# PowerRouting.net
KiCad netlist of a schematic drawn in Altium Designer
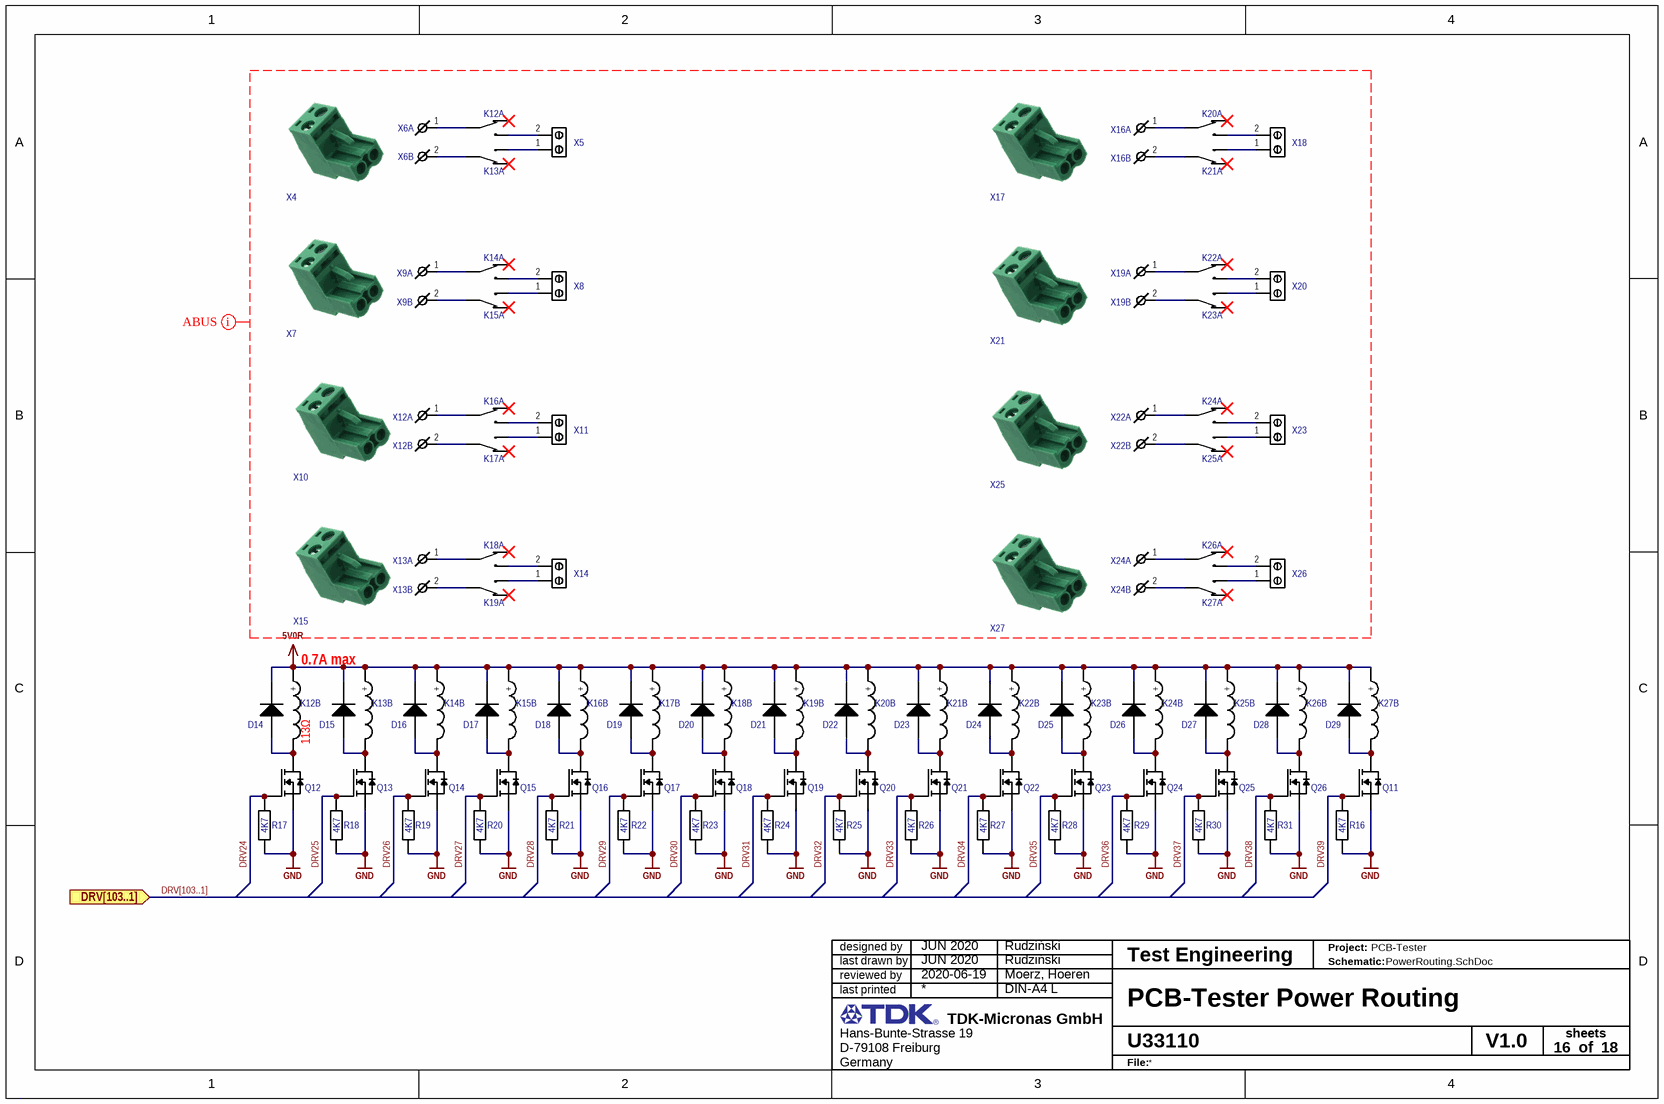
[diagram p0: PowerRouting.SchDoc]

(export (version "E")
  (design (tool "Eeschema 10.0.6"))
  (components
    (comp (ref "D14")
      (value "D")
      (footprint "SOD123")
      (description "DIODE GEN PURP 100V 300MA SOD123")
      (fields
        (field (name "02. DISTRIBUTOR PART NUMBER") "1N4148W-FDICT-ND")
        (field (name "07. MANUFACTURER  PART NUMBER") "1N4148W-7-F")
      )
      (libsource (lib "PCB-Tester-Board-V1") (part "1N4148W"))
    )
    (comp (ref "D15")
      (value "D")
      (footprint "SOD123")
      (description "DIODE GEN PURP 100V 300MA SOD123")
      (fields
        (field (name "02. DISTRIBUTOR PART NUMBER") "1N4148W-FDICT-ND")
        (field (name "07. MANUFACTURER  PART NUMBER") "1N4148W-7-F")
      )
      (libsource (lib "PCB-Tester-Board-V1") (part "1N4148W"))
    )
    (comp (ref "D16")
      (value "D")
      (footprint "SOD123")
      (description "DIODE GEN PURP 100V 300MA SOD123")
      (fields
        (field (name "02. DISTRIBUTOR PART NUMBER") "1N4148W-FDICT-ND")
        (field (name "07. MANUFACTURER  PART NUMBER") "1N4148W-7-F")
      )
      (libsource (lib "PCB-Tester-Board-V1") (part "1N4148W"))
    )
    (comp (ref "D17")
      (value "D")
      (footprint "SOD123")
      (description "DIODE GEN PURP 100V 300MA SOD123")
      (fields
        (field (name "02. DISTRIBUTOR PART NUMBER") "1N4148W-FDICT-ND")
        (field (name "07. MANUFACTURER  PART NUMBER") "1N4148W-7-F")
      )
      (libsource (lib "PCB-Tester-Board-V1") (part "1N4148W"))
    )
    (comp (ref "D18")
      (value "D")
      (footprint "SOD123")
      (description "DIODE GEN PURP 100V 300MA SOD123")
      (fields
        (field (name "02. DISTRIBUTOR PART NUMBER") "1N4148W-FDICT-ND")
        (field (name "07. MANUFACTURER  PART NUMBER") "1N4148W-7-F")
      )
      (libsource (lib "PCB-Tester-Board-V1") (part "1N4148W"))
    )
    (comp (ref "D19")
      (value "D")
      (footprint "SOD123")
      (description "DIODE GEN PURP 100V 300MA SOD123")
      (fields
        (field (name "02. DISTRIBUTOR PART NUMBER") "1N4148W-FDICT-ND")
        (field (name "07. MANUFACTURER  PART NUMBER") "1N4148W-7-F")
      )
      (libsource (lib "PCB-Tester-Board-V1") (part "1N4148W"))
    )
    (comp (ref "D20")
      (value "D")
      (footprint "SOD123")
      (description "DIODE GEN PURP 100V 300MA SOD123")
      (fields
        (field (name "02. DISTRIBUTOR PART NUMBER") "1N4148W-FDICT-ND")
        (field (name "07. MANUFACTURER  PART NUMBER") "1N4148W-7-F")
      )
      (libsource (lib "PCB-Tester-Board-V1") (part "1N4148W"))
    )
    (comp (ref "D21")
      (value "D")
      (footprint "SOD123")
      (description "DIODE GEN PURP 100V 300MA SOD123")
      (fields
        (field (name "02. DISTRIBUTOR PART NUMBER") "1N4148W-FDICT-ND")
        (field (name "07. MANUFACTURER  PART NUMBER") "1N4148W-7-F")
      )
      (libsource (lib "PCB-Tester-Board-V1") (part "1N4148W"))
    )
    (comp (ref "D22")
      (value "D")
      (footprint "SOD123")
      (description "DIODE GEN PURP 100V 300MA SOD123")
      (fields
        (field (name "02. DISTRIBUTOR PART NUMBER") "1N4148W-FDICT-ND")
        (field (name "07. MANUFACTURER  PART NUMBER") "1N4148W-7-F")
      )
      (libsource (lib "PCB-Tester-Board-V1") (part "1N4148W"))
    )
    (comp (ref "D23")
      (value "D")
      (footprint "SOD123")
      (description "DIODE GEN PURP 100V 300MA SOD123")
      (fields
        (field (name "02. DISTRIBUTOR PART NUMBER") "1N4148W-FDICT-ND")
        (field (name "07. MANUFACTURER  PART NUMBER") "1N4148W-7-F")
      )
      (libsource (lib "PCB-Tester-Board-V1") (part "1N4148W"))
    )
    (comp (ref "D24")
      (value "D")
      (footprint "SOD123")
      (description "DIODE GEN PURP 100V 300MA SOD123")
      (fields
        (field (name "02. DISTRIBUTOR PART NUMBER") "1N4148W-FDICT-ND")
        (field (name "07. MANUFACTURER  PART NUMBER") "1N4148W-7-F")
      )
      (libsource (lib "PCB-Tester-Board-V1") (part "1N4148W"))
    )
    (comp (ref "D25")
      (value "D")
      (footprint "SOD123")
      (description "DIODE GEN PURP 100V 300MA SOD123")
      (fields
        (field (name "02. DISTRIBUTOR PART NUMBER") "1N4148W-FDICT-ND")
        (field (name "07. MANUFACTURER  PART NUMBER") "1N4148W-7-F")
      )
      (libsource (lib "PCB-Tester-Board-V1") (part "1N4148W"))
    )
    (comp (ref "D26")
      (value "D")
      (footprint "SOD123")
      (description "DIODE GEN PURP 100V 300MA SOD123")
      (fields
        (field (name "02. DISTRIBUTOR PART NUMBER") "1N4148W-FDICT-ND")
        (field (name "07. MANUFACTURER  PART NUMBER") "1N4148W-7-F")
      )
      (libsource (lib "PCB-Tester-Board-V1") (part "1N4148W"))
    )
    (comp (ref "D27")
      (value "D")
      (footprint "SOD123")
      (description "DIODE GEN PURP 100V 300MA SOD123")
      (fields
        (field (name "02. DISTRIBUTOR PART NUMBER") "1N4148W-FDICT-ND")
        (field (name "07. MANUFACTURER  PART NUMBER") "1N4148W-7-F")
      )
      (libsource (lib "PCB-Tester-Board-V1") (part "1N4148W"))
    )
    (comp (ref "D28")
      (value "D")
      (footprint "SOD123")
      (description "DIODE GEN PURP 100V 300MA SOD123")
      (fields
        (field (name "02. DISTRIBUTOR PART NUMBER") "1N4148W-FDICT-ND")
        (field (name "07. MANUFACTURER  PART NUMBER") "1N4148W-7-F")
      )
      (libsource (lib "PCB-Tester-Board-V1") (part "1N4148W"))
    )
    (comp (ref "D29")
      (value "D")
      (footprint "SOD123")
      (description "DIODE GEN PURP 100V 300MA SOD123")
      (fields
        (field (name "02. DISTRIBUTOR PART NUMBER") "1N4148W-FDICT-ND")
        (field (name "07. MANUFACTURER  PART NUMBER") "1N4148W-7-F")
      )
      (libsource (lib "PCB-Tester-Board-V1") (part "1N4148W"))
    )
    (comp (ref "K12")
      (value "K")
      (footprint "HF118F005-1ZS1")
      (description "5V Power Relay, switch over")
      (fields
        (field (name "02. DISTRIBUTOR PART NUMBER") "176-2821")
        (field (name "07. MANUFACTURER  PART NUMBER") "HF118F/005-1ZS1T(136)")
        (field (name "COIL RESISTANCE") "113Ω")
        (field (name "13. CREATED DATE/NAME") "AUG2018/Hören")
      )
      (libsource (lib "chickenfood") (part "HF118F005-1ZS1"))
    )
    (comp (ref "K13")
      (value "K")
      (footprint "HF118F005-1ZS1")
      (description "5V Power Relay, switch over")
      (fields
        (field (name "02. DISTRIBUTOR PART NUMBER") "176-2821")
        (field (name "07. MANUFACTURER  PART NUMBER") "HF118F/005-1ZS1T(136)")
        (field (name "13. CREATED DATE/NAME") "AUG2018/Hören")
      )
      (libsource (lib "") (part "HF118F005-1ZS1_1"))
    )
    (comp (ref "K14")
      (value "K")
      (footprint "HF118F005-1ZS1")
      (description "5V Power Relay, switch over")
      (fields
        (field (name "02. DISTRIBUTOR PART NUMBER") "176-2821")
        (field (name "07. MANUFACTURER  PART NUMBER") "HF118F/005-1ZS1T(136)")
        (field (name "13. CREATED DATE/NAME") "AUG2018/Hören")
      )
      (libsource (lib "chickenfood") (part "HF118F005-1ZS1"))
    )
    (comp (ref "K15")
      (value "K")
      (footprint "HF118F005-1ZS1")
      (description "5V Power Relay, switch over")
      (fields
        (field (name "02. DISTRIBUTOR PART NUMBER") "176-2821")
        (field (name "07. MANUFACTURER  PART NUMBER") "HF118F/005-1ZS1T(136)")
        (field (name "13. CREATED DATE/NAME") "AUG2018/Hören")
      )
      (libsource (lib "chickenfood") (part "HF118F005-1ZS1"))
    )
    (comp (ref "K16")
      (value "K")
      (footprint "HF118F005-1ZS1")
      (description "5V Power Relay, switch over")
      (fields
        (field (name "02. DISTRIBUTOR PART NUMBER") "176-2821")
        (field (name "07. MANUFACTURER  PART NUMBER") "HF118F/005-1ZS1T(136)")
        (field (name "13. CREATED DATE/NAME") "AUG2018/Hören")
      )
      (libsource (lib "chickenfood") (part "HF118F005-1ZS1"))
    )
    (comp (ref "K17")
      (value "K")
      (footprint "HF118F005-1ZS1")
      (description "5V Power Relay, switch over")
      (fields
        (field (name "02. DISTRIBUTOR PART NUMBER") "176-2821")
        (field (name "07. MANUFACTURER  PART NUMBER") "HF118F/005-1ZS1T(136)")
        (field (name "13. CREATED DATE/NAME") "AUG2018/Hören")
      )
      (libsource (lib "") (part "HF118F005-1ZS1_1"))
    )
    (comp (ref "K18")
      (value "K")
      (footprint "HF118F005-1ZS1")
      (description "5V Power Relay, switch over")
      (fields
        (field (name "02. DISTRIBUTOR PART NUMBER") "176-2821")
        (field (name "07. MANUFACTURER  PART NUMBER") "HF118F/005-1ZS1T(136)")
        (field (name "13. CREATED DATE/NAME") "AUG2018/Hören")
      )
      (libsource (lib "chickenfood") (part "HF118F005-1ZS1"))
    )
    (comp (ref "K19")
      (value "K")
      (footprint "HF118F005-1ZS1")
      (description "5V Power Relay, switch over")
      (fields
        (field (name "02. DISTRIBUTOR PART NUMBER") "176-2821")
        (field (name "07. MANUFACTURER  PART NUMBER") "HF118F/005-1ZS1T(136)")
        (field (name "13. CREATED DATE/NAME") "AUG2018/Hören")
      )
      (libsource (lib "chickenfood") (part "HF118F005-1ZS1"))
    )
    (comp (ref "K20")
      (value "K")
      (footprint "HF118F005-1ZS1")
      (description "5V Power Relay, switch over")
      (fields
        (field (name "02. DISTRIBUTOR PART NUMBER") "176-2821")
        (field (name "07. MANUFACTURER  PART NUMBER") "HF118F/005-1ZS1T(136)")
        (field (name "13. CREATED DATE/NAME") "AUG2018/Hören")
      )
      (libsource (lib "chickenfood") (part "HF118F005-1ZS1"))
    )
    (comp (ref "K21")
      (value "K")
      (footprint "HF118F005-1ZS1")
      (description "5V Power Relay, switch over")
      (fields
        (field (name "02. DISTRIBUTOR PART NUMBER") "176-2821")
        (field (name "07. MANUFACTURER  PART NUMBER") "HF118F/005-1ZS1T(136)")
        (field (name "13. CREATED DATE/NAME") "AUG2018/Hören")
      )
      (libsource (lib "chickenfood") (part "HF118F005-1ZS1"))
    )
    (comp (ref "K22")
      (value "K")
      (footprint "HF118F005-1ZS1")
      (description "5V Power Relay, switch over")
      (fields
        (field (name "02. DISTRIBUTOR PART NUMBER") "176-2821")
        (field (name "07. MANUFACTURER  PART NUMBER") "HF118F/005-1ZS1T(136)")
        (field (name "13. CREATED DATE/NAME") "AUG2018/Hören")
      )
      (libsource (lib "chickenfood") (part "HF118F005-1ZS1"))
    )
    (comp (ref "K23")
      (value "K")
      (footprint "HF118F005-1ZS1")
      (description "5V Power Relay, switch over")
      (fields
        (field (name "02. DISTRIBUTOR PART NUMBER") "176-2821")
        (field (name "07. MANUFACTURER  PART NUMBER") "HF118F/005-1ZS1T(136)")
        (field (name "13. CREATED DATE/NAME") "AUG2018/Hören")
      )
      (libsource (lib "chickenfood") (part "HF118F005-1ZS1"))
    )
    (comp (ref "K24")
      (value "K")
      (footprint "HF118F005-1ZS1")
      (description "5V Power Relay, switch over")
      (fields
        (field (name "02. DISTRIBUTOR PART NUMBER") "176-2821")
        (field (name "07. MANUFACTURER  PART NUMBER") "HF118F/005-1ZS1T(136)")
        (field (name "13. CREATED DATE/NAME") "AUG2018/Hören")
      )
      (libsource (lib "chickenfood") (part "HF118F005-1ZS1"))
    )
    (comp (ref "K25")
      (value "K")
      (footprint "HF118F005-1ZS1")
      (description "5V Power Relay, switch over")
      (fields
        (field (name "02. DISTRIBUTOR PART NUMBER") "176-2821")
        (field (name "07. MANUFACTURER  PART NUMBER") "HF118F/005-1ZS1T(136)")
        (field (name "13. CREATED DATE/NAME") "AUG2018/Hören")
      )
      (libsource (lib "") (part "HF118F005-1ZS1_1"))
    )
    (comp (ref "K26")
      (value "K")
      (footprint "HF118F005-1ZS1")
      (description "5V Power Relay, switch over")
      (fields
        (field (name "02. DISTRIBUTOR PART NUMBER") "176-2821")
        (field (name "07. MANUFACTURER  PART NUMBER") "HF118F/005-1ZS1T(136)")
        (field (name "13. CREATED DATE/NAME") "AUG2018/Hören")
      )
      (libsource (lib "chickenfood") (part "HF118F005-1ZS1"))
    )
    (comp (ref "K27")
      (value "K")
      (footprint "HF118F005-1ZS1")
      (description "5V Power Relay, switch over")
      (fields
        (field (name "02. DISTRIBUTOR PART NUMBER") "176-2821")
        (field (name "07. MANUFACTURER  PART NUMBER") "HF118F/005-1ZS1T(136)")
        (field (name "13. CREATED DATE/NAME") "AUG2018/Hören")
      )
      (libsource (lib "") (part "HF118F005-1ZS1_1"))
    )
    (comp (ref "Q11")
      (value "Q")
      (footprint "SOT23-3")
      (description "MOSFET N-CH 25V 680MA SOT-23")
      (fields
        (field (name "02. DISTRIBUTOR PART NUMBER") "FDV303NDKR-ND")
        (field (name "07. MANUFACTURER  PART NUMBER") "FDV303N")
        (field (name "13. CREATED DATE/NAME") "AUG 2018 / Hören")
      )
      (libsource (lib "SCT8-Board1") (part "FDV303N"))
    )
    (comp (ref "Q12")
      (value "Q")
      (footprint "SOT23-3")
      (description "MOSFET N-CH 25V 680MA SOT-23")
      (fields
        (field (name "02. DISTRIBUTOR PART NUMBER") "FDV303NDKR-ND")
        (field (name "07. MANUFACTURER  PART NUMBER") "FDV303N")
        (field (name "13. CREATED DATE/NAME") "AUG 2018 / Hören")
      )
      (libsource (lib "SCT8-Board1") (part "FDV303N"))
    )
    (comp (ref "Q13")
      (value "Q")
      (footprint "SOT23-3")
      (description "MOSFET N-CH 25V 680MA SOT-23")
      (fields
        (field (name "02. DISTRIBUTOR PART NUMBER") "FDV303NDKR-ND")
        (field (name "07. MANUFACTURER  PART NUMBER") "FDV303N")
        (field (name "13. CREATED DATE/NAME") "AUG 2018 / Hören")
      )
      (libsource (lib "SCT8-Board1") (part "FDV303N"))
    )
    (comp (ref "Q14")
      (value "Q")
      (footprint "SOT23-3")
      (description "MOSFET N-CH 25V 680MA SOT-23")
      (fields
        (field (name "02. DISTRIBUTOR PART NUMBER") "FDV303NDKR-ND")
        (field (name "07. MANUFACTURER  PART NUMBER") "FDV303N")
        (field (name "13. CREATED DATE/NAME") "AUG 2018 / Hören")
      )
      (libsource (lib "SCT8-Board1") (part "FDV303N"))
    )
    (comp (ref "Q15")
      (value "Q")
      (footprint "SOT23-3")
      (description "MOSFET N-CH 25V 680MA SOT-23")
      (fields
        (field (name "02. DISTRIBUTOR PART NUMBER") "FDV303NDKR-ND")
        (field (name "07. MANUFACTURER  PART NUMBER") "FDV303N")
        (field (name "13. CREATED DATE/NAME") "AUG 2018 / Hören")
      )
      (libsource (lib "SCT8-Board1") (part "FDV303N"))
    )
    (comp (ref "Q16")
      (value "Q")
      (footprint "SOT23-3")
      (description "MOSFET N-CH 25V 680MA SOT-23")
      (fields
        (field (name "02. DISTRIBUTOR PART NUMBER") "FDV303NDKR-ND")
        (field (name "07. MANUFACTURER  PART NUMBER") "FDV303N")
        (field (name "13. CREATED DATE/NAME") "AUG 2018 / Hören")
      )
      (libsource (lib "SCT8-Board1") (part "FDV303N"))
    )
    (comp (ref "Q17")
      (value "Q")
      (footprint "SOT23-3")
      (description "MOSFET N-CH 25V 680MA SOT-23")
      (fields
        (field (name "02. DISTRIBUTOR PART NUMBER") "FDV303NDKR-ND")
        (field (name "07. MANUFACTURER  PART NUMBER") "FDV303N")
        (field (name "13. CREATED DATE/NAME") "AUG 2018 / Hören")
      )
      (libsource (lib "SCT8-Board1") (part "FDV303N"))
    )
    (comp (ref "Q18")
      (value "Q")
      (footprint "SOT23-3")
      (description "MOSFET N-CH 25V 680MA SOT-23")
      (fields
        (field (name "02. DISTRIBUTOR PART NUMBER") "FDV303NDKR-ND")
        (field (name "07. MANUFACTURER  PART NUMBER") "FDV303N")
        (field (name "13. CREATED DATE/NAME") "AUG 2018 / Hören")
      )
      (libsource (lib "SCT8-Board1") (part "FDV303N"))
    )
    (comp (ref "Q19")
      (value "Q")
      (footprint "SOT23-3")
      (description "MOSFET N-CH 25V 680MA SOT-23")
      (fields
        (field (name "02. DISTRIBUTOR PART NUMBER") "FDV303NDKR-ND")
        (field (name "07. MANUFACTURER  PART NUMBER") "FDV303N")
        (field (name "13. CREATED DATE/NAME") "AUG 2018 / Hören")
      )
      (libsource (lib "SCT8-Board1") (part "FDV303N"))
    )
    (comp (ref "Q20")
      (value "Q")
      (footprint "SOT23-3")
      (description "MOSFET N-CH 25V 680MA SOT-23")
      (fields
        (field (name "02. DISTRIBUTOR PART NUMBER") "FDV303NDKR-ND")
        (field (name "07. MANUFACTURER  PART NUMBER") "FDV303N")
        (field (name "13. CREATED DATE/NAME") "AUG 2018 / Hören")
      )
      (libsource (lib "SCT8-Board1") (part "FDV303N"))
    )
    (comp (ref "Q21")
      (value "Q")
      (footprint "SOT23-3")
      (description "MOSFET N-CH 25V 680MA SOT-23")
      (fields
        (field (name "02. DISTRIBUTOR PART NUMBER") "FDV303NDKR-ND")
        (field (name "07. MANUFACTURER  PART NUMBER") "FDV303N")
        (field (name "13. CREATED DATE/NAME") "AUG 2018 / Hören")
      )
      (libsource (lib "SCT8-Board1") (part "FDV303N"))
    )
    (comp (ref "Q22")
      (value "Q")
      (footprint "SOT23-3")
      (description "MOSFET N-CH 25V 680MA SOT-23")
      (fields
        (field (name "02. DISTRIBUTOR PART NUMBER") "FDV303NDKR-ND")
        (field (name "07. MANUFACTURER  PART NUMBER") "FDV303N")
        (field (name "13. CREATED DATE/NAME") "AUG 2018 / Hören")
      )
      (libsource (lib "SCT8-Board1") (part "FDV303N"))
    )
    (comp (ref "Q23")
      (value "Q")
      (footprint "SOT23-3")
      (description "MOSFET N-CH 25V 680MA SOT-23")
      (fields
        (field (name "02. DISTRIBUTOR PART NUMBER") "FDV303NDKR-ND")
        (field (name "07. MANUFACTURER  PART NUMBER") "FDV303N")
        (field (name "13. CREATED DATE/NAME") "AUG 2018 / Hören")
      )
      (libsource (lib "SCT8-Board1") (part "FDV303N"))
    )
    (comp (ref "Q24")
      (value "Q")
      (footprint "SOT23-3")
      (description "MOSFET N-CH 25V 680MA SOT-23")
      (fields
        (field (name "02. DISTRIBUTOR PART NUMBER") "FDV303NDKR-ND")
        (field (name "07. MANUFACTURER  PART NUMBER") "FDV303N")
        (field (name "13. CREATED DATE/NAME") "AUG 2018 / Hören")
      )
      (libsource (lib "SCT8-Board1") (part "FDV303N"))
    )
    (comp (ref "Q25")
      (value "Q")
      (footprint "SOT23-3")
      (description "MOSFET N-CH 25V 680MA SOT-23")
      (fields
        (field (name "02. DISTRIBUTOR PART NUMBER") "FDV303NDKR-ND")
        (field (name "07. MANUFACTURER  PART NUMBER") "FDV303N")
        (field (name "13. CREATED DATE/NAME") "AUG 2018 / Hören")
      )
      (libsource (lib "SCT8-Board1") (part "FDV303N"))
    )
    (comp (ref "Q26")
      (value "Q")
      (footprint "SOT23-3")
      (description "MOSFET N-CH 25V 680MA SOT-23")
      (fields
        (field (name "02. DISTRIBUTOR PART NUMBER") "FDV303NDKR-ND")
        (field (name "07. MANUFACTURER  PART NUMBER") "FDV303N")
        (field (name "13. CREATED DATE/NAME") "AUG 2018 / Hören")
      )
      (libsource (lib "SCT8-Board1") (part "FDV303N"))
    )
    (comp (ref "R16")
      (value "4K7")
      (footprint "R0603 Reflow")
      (description "RES SMD 4.7K OHM 1% 1/10W 0603")
      (fields
        (field (name "TOLERANCE") "±1%")
        (field (name "02. DISTRIBUTOR PART NUMBER") "311-4.70KHRCT-ND")
        (field (name "13. CREATED DATE/NAME") "AUG2018/Hören")
      )
      (libsource (lib "chickenfood") (part "R"))
    )
    (comp (ref "R17")
      (value "4K7")
      (footprint "R0603 Reflow")
      (description "RES SMD 4.7K OHM 1% 1/10W 0603")
      (fields
        (field (name "TOLERANCE") "±1%")
        (field (name "02. DISTRIBUTOR PART NUMBER") "311-4.70KHRCT-ND")
        (field (name "13. CREATED DATE/NAME") "AUG2018/Hören")
      )
      (libsource (lib "chickenfood") (part "R"))
    )
    (comp (ref "R18")
      (value "4K7")
      (footprint "R0603 Reflow")
      (description "RES SMD 4.7K OHM 1% 1/10W 0603")
      (fields
        (field (name "TOLERANCE") "±1%")
        (field (name "02. DISTRIBUTOR PART NUMBER") "311-4.70KHRCT-ND")
        (field (name "13. CREATED DATE/NAME") "AUG2018/Hören")
      )
      (libsource (lib "chickenfood") (part "R"))
    )
    (comp (ref "R19")
      (value "4K7")
      (footprint "R0603 Reflow")
      (description "RES SMD 4.7K OHM 1% 1/10W 0603")
      (fields
        (field (name "TOLERANCE") "±1%")
        (field (name "02. DISTRIBUTOR PART NUMBER") "311-4.70KHRCT-ND")
        (field (name "13. CREATED DATE/NAME") "AUG2018/Hören")
      )
      (libsource (lib "chickenfood") (part "R"))
    )
    (comp (ref "R20")
      (value "4K7")
      (footprint "R0603 Reflow")
      (description "RES SMD 4.7K OHM 1% 1/10W 0603")
      (fields
        (field (name "TOLERANCE") "±1%")
        (field (name "02. DISTRIBUTOR PART NUMBER") "311-4.70KHRCT-ND")
        (field (name "13. CREATED DATE/NAME") "AUG2018/Hören")
      )
      (libsource (lib "chickenfood") (part "R"))
    )
    (comp (ref "R21")
      (value "4K7")
      (footprint "R0603 Reflow")
      (description "RES SMD 4.7K OHM 1% 1/10W 0603")
      (fields
        (field (name "TOLERANCE") "±1%")
        (field (name "02. DISTRIBUTOR PART NUMBER") "311-4.70KHRCT-ND")
        (field (name "13. CREATED DATE/NAME") "AUG2018/Hören")
      )
      (libsource (lib "chickenfood") (part "R"))
    )
    (comp (ref "R22")
      (value "4K7")
      (footprint "R0603 Reflow")
      (description "RES SMD 4.7K OHM 1% 1/10W 0603")
      (fields
        (field (name "TOLERANCE") "±1%")
        (field (name "02. DISTRIBUTOR PART NUMBER") "311-4.70KHRCT-ND")
        (field (name "13. CREATED DATE/NAME") "AUG2018/Hören")
      )
      (libsource (lib "chickenfood") (part "R"))
    )
    (comp (ref "R23")
      (value "4K7")
      (footprint "R0603 Reflow")
      (description "RES SMD 4.7K OHM 1% 1/10W 0603")
      (fields
        (field (name "TOLERANCE") "±1%")
        (field (name "02. DISTRIBUTOR PART NUMBER") "311-4.70KHRCT-ND")
        (field (name "13. CREATED DATE/NAME") "AUG2018/Hören")
      )
      (libsource (lib "chickenfood") (part "R"))
    )
    (comp (ref "R24")
      (value "4K7")
      (footprint "R0603 Reflow")
      (description "RES SMD 4.7K OHM 1% 1/10W 0603")
      (fields
        (field (name "TOLERANCE") "±1%")
        (field (name "02. DISTRIBUTOR PART NUMBER") "311-4.70KHRCT-ND")
        (field (name "13. CREATED DATE/NAME") "AUG2018/Hören")
      )
      (libsource (lib "chickenfood") (part "R"))
    )
    (comp (ref "R25")
      (value "4K7")
      (footprint "R0603 Reflow")
      (description "RES SMD 4.7K OHM 1% 1/10W 0603")
      (fields
        (field (name "TOLERANCE") "±1%")
        (field (name "02. DISTRIBUTOR PART NUMBER") "311-4.70KHRCT-ND")
        (field (name "13. CREATED DATE/NAME") "AUG2018/Hören")
      )
      (libsource (lib "chickenfood") (part "R"))
    )
    (comp (ref "R26")
      (value "4K7")
      (footprint "R0603 Reflow")
      (description "RES SMD 4.7K OHM 1% 1/10W 0603")
      (fields
        (field (name "TOLERANCE") "±1%")
        (field (name "02. DISTRIBUTOR PART NUMBER") "311-4.70KHRCT-ND")
        (field (name "13. CREATED DATE/NAME") "AUG2018/Hören")
      )
      (libsource (lib "chickenfood") (part "R"))
    )
    (comp (ref "R27")
      (value "4K7")
      (footprint "R0603 Reflow")
      (description "RES SMD 4.7K OHM 1% 1/10W 0603")
      (fields
        (field (name "TOLERANCE") "±1%")
        (field (name "02. DISTRIBUTOR PART NUMBER") "311-4.70KHRCT-ND")
        (field (name "13. CREATED DATE/NAME") "AUG2018/Hören")
      )
      (libsource (lib "chickenfood") (part "R"))
    )
    (comp (ref "R28")
      (value "4K7")
      (footprint "R0603 Reflow")
      (description "RES SMD 4.7K OHM 1% 1/10W 0603")
      (fields
        (field (name "TOLERANCE") "±1%")
        (field (name "02. DISTRIBUTOR PART NUMBER") "311-4.70KHRCT-ND")
        (field (name "13. CREATED DATE/NAME") "AUG2018/Hören")
      )
      (libsource (lib "chickenfood") (part "R"))
    )
    (comp (ref "R29")
      (value "4K7")
      (footprint "R0603 Reflow")
      (description "RES SMD 4.7K OHM 1% 1/10W 0603")
      (fields
        (field (name "TOLERANCE") "±1%")
        (field (name "02. DISTRIBUTOR PART NUMBER") "311-4.70KHRCT-ND")
        (field (name "13. CREATED DATE/NAME") "AUG2018/Hören")
      )
      (libsource (lib "chickenfood") (part "R"))
    )
    (comp (ref "R30")
      (value "4K7")
      (footprint "R0603 Reflow")
      (description "RES SMD 4.7K OHM 1% 1/10W 0603")
      (fields
        (field (name "TOLERANCE") "±1%")
        (field (name "02. DISTRIBUTOR PART NUMBER") "311-4.70KHRCT-ND")
        (field (name "13. CREATED DATE/NAME") "AUG2018/Hören")
      )
      (libsource (lib "chickenfood") (part "R"))
    )
    (comp (ref "R31")
      (value "4K7")
      (footprint "R0603 Reflow")
      (description "RES SMD 4.7K OHM 1% 1/10W 0603")
      (fields
        (field (name "TOLERANCE") "±1%")
        (field (name "02. DISTRIBUTOR PART NUMBER") "311-4.70KHRCT-ND")
        (field (name "13. CREATED DATE/NAME") "AUG2018/Hören")
      )
      (libsource (lib "chickenfood") (part "R"))
    )
    (comp (ref "X4")
      (value "X")
      (footprint "691352710002")
      (description "TERM BLOCK PLUG 2POS STR 5MM")
      (fields
        (field (name "02. DISTRIBUTOR PART NUMBER") "732-2775-ND")
        (field (name "07. MANUFACTURER  PART NUMBER") "691352710002")
        (field (name "13. CREATED DATE/NAME") "??? / Hören")
      )
      (libsource (lib "PCB-Tester-Board-V1") (part "691352710002"))
    )
    (comp (ref "X5")
      (value "X")
      (footprint "1731721")
      (description "TERM BLK 2P SIDE ENT 7.62MM PCB")
      (fields
        (field (name "02. DISTRIBUTOR PART NUMBER") "277-5849-ND")
        (field (name "07. MANUFACTURER  PART NUMBER") "1731721")
        (field (name "13. CREATED DATE/NAME") "JAN 2019 / Hören")
      )
      (libsource (lib "Connectors") (part "1731721"))
    )
    (comp (ref "X6")
      (value "X")
      (footprint "691312710002")
      (description "TERM BLOCK HDR 2POS 90DEG 5MM")
      (fields
        (field (name "02. DISTRIBUTOR PART NUMBER") "732-2805-ND")
        (field (name "07. MANUFACTURER  PART NUMBER") "691312710002")
        (field (name "13. CREATED DATE/NAME") "??? / Hören")
      )
      (libsource (lib "Connectors") (part "691312710002"))
    )
    (comp (ref "X7")
      (value "X")
      (footprint "691352710002")
      (description "TERM BLOCK PLUG 2POS STR 5MM")
      (fields
        (field (name "02. DISTRIBUTOR PART NUMBER") "732-2775-ND")
        (field (name "07. MANUFACTURER  PART NUMBER") "691352710002")
        (field (name "13. CREATED DATE/NAME") "??? / Hören")
      )
      (libsource (lib "PCB-Tester-Board-V1") (part "691352710002"))
    )
    (comp (ref "X8")
      (value "X")
      (footprint "1731721")
      (description "TERM BLK 2P SIDE ENT 7.62MM PCB")
      (fields
        (field (name "02. DISTRIBUTOR PART NUMBER") "277-5849-ND")
        (field (name "07. MANUFACTURER  PART NUMBER") "1731721")
        (field (name "13. CREATED DATE/NAME") "JAN 2019 / Hören")
      )
      (libsource (lib "Connectors") (part "1731721"))
    )
    (comp (ref "X9")
      (value "X")
      (footprint "691312710002")
      (description "TERM BLOCK HDR 2POS 90DEG 5MM")
      (fields
        (field (name "02. DISTRIBUTOR PART NUMBER") "732-2805-ND")
        (field (name "07. MANUFACTURER  PART NUMBER") "691312710002")
        (field (name "13. CREATED DATE/NAME") "??? / Hören")
      )
      (libsource (lib "Connectors") (part "691312710002"))
    )
    (comp (ref "X10")
      (value "X")
      (footprint "691352710002")
      (description "TERM BLOCK PLUG 2POS STR 5MM")
      (fields
        (field (name "02. DISTRIBUTOR PART NUMBER") "732-2775-ND")
        (field (name "07. MANUFACTURER  PART NUMBER") "691352710002")
        (field (name "13. CREATED DATE/NAME") "??? / Hören")
      )
      (libsource (lib "PCB-Tester-Board-V1") (part "691352710002"))
    )
    (comp (ref "X11")
      (value "X")
      (footprint "1731721")
      (description "TERM BLK 2P SIDE ENT 7.62MM PCB")
      (fields
        (field (name "02. DISTRIBUTOR PART NUMBER") "277-5849-ND")
        (field (name "07. MANUFACTURER  PART NUMBER") "1731721")
        (field (name "13. CREATED DATE/NAME") "JAN 2019 / Hören")
      )
      (libsource (lib "Connectors") (part "1731721"))
    )
    (comp (ref "X12")
      (value "X")
      (footprint "691312710002")
      (description "TERM BLOCK HDR 2POS 90DEG 5MM")
      (fields
        (field (name "02. DISTRIBUTOR PART NUMBER") "732-2805-ND")
        (field (name "07. MANUFACTURER  PART NUMBER") "691312710002")
        (field (name "13. CREATED DATE/NAME") "??? / Hören")
      )
      (libsource (lib "Connectors") (part "691312710002"))
    )
    (comp (ref "X13")
      (value "X")
      (footprint "691312710002")
      (description "TERM BLOCK HDR 2POS 90DEG 5MM")
      (fields
        (field (name "02. DISTRIBUTOR PART NUMBER") "732-2805-ND")
        (field (name "07. MANUFACTURER  PART NUMBER") "691312710002")
        (field (name "13. CREATED DATE/NAME") "??? / Hören")
      )
      (libsource (lib "Connectors") (part "691312710002"))
    )
    (comp (ref "X14")
      (value "X")
      (footprint "1731721")
      (description "TERM BLK 2P SIDE ENT 7.62MM PCB")
      (fields
        (field (name "02. DISTRIBUTOR PART NUMBER") "277-5849-ND")
        (field (name "07. MANUFACTURER  PART NUMBER") "1731721")
        (field (name "13. CREATED DATE/NAME") "JAN 2019 / Hören")
      )
      (libsource (lib "Connectors") (part "1731721"))
    )
    (comp (ref "X15")
      (value "X")
      (footprint "691352710002")
      (description "TERM BLOCK PLUG 2POS STR 5MM")
      (fields
        (field (name "02. DISTRIBUTOR PART NUMBER") "732-2775-ND")
        (field (name "07. MANUFACTURER  PART NUMBER") "691352710002")
        (field (name "13. CREATED DATE/NAME") "??? / Hören")
      )
      (libsource (lib "PCB-Tester-Board-V1") (part "691352710002"))
    )
    (comp (ref "X16")
      (value "X")
      (footprint "691312710002")
      (description "TERM BLOCK HDR 2POS 90DEG 5MM")
      (fields
        (field (name "02. DISTRIBUTOR PART NUMBER") "732-2805-ND")
        (field (name "07. MANUFACTURER  PART NUMBER") "691312710002")
        (field (name "13. CREATED DATE/NAME") "??? / Hören")
      )
      (libsource (lib "Connectors") (part "691312710002"))
    )
    (comp (ref "X17")
      (value "X")
      (footprint "691352710002")
      (description "TERM BLOCK PLUG 2POS STR 5MM")
      (fields
        (field (name "02. DISTRIBUTOR PART NUMBER") "732-2775-ND")
        (field (name "07. MANUFACTURER  PART NUMBER") "691352710002")
        (field (name "13. CREATED DATE/NAME") "??? / Hören")
      )
      (libsource (lib "PCB-Tester-Board-V1") (part "691352710002"))
    )
    (comp (ref "X18")
      (value "X")
      (footprint "1731721")
      (description "TERM BLK 2P SIDE ENT 7.62MM PCB")
      (fields
        (field (name "02. DISTRIBUTOR PART NUMBER") "277-5849-ND")
        (field (name "07. MANUFACTURER  PART NUMBER") "1731721")
        (field (name "13. CREATED DATE/NAME") "JAN 2019 / Hören")
      )
      (libsource (lib "Connectors") (part "1731721"))
    )
    (comp (ref "X19")
      (value "X")
      (footprint "691312710002")
      (description "TERM BLOCK HDR 2POS 90DEG 5MM")
      (fields
        (field (name "02. DISTRIBUTOR PART NUMBER") "732-2805-ND")
        (field (name "07. MANUFACTURER  PART NUMBER") "691312710002")
        (field (name "13. CREATED DATE/NAME") "??? / Hören")
      )
      (libsource (lib "Connectors") (part "691312710002"))
    )
    (comp (ref "X20")
      (value "X")
      (footprint "1731721")
      (description "TERM BLK 2P SIDE ENT 7.62MM PCB")
      (fields
        (field (name "02. DISTRIBUTOR PART NUMBER") "277-5849-ND")
        (field (name "07. MANUFACTURER  PART NUMBER") "1731721")
        (field (name "13. CREATED DATE/NAME") "JAN 2019 / Hören")
      )
      (libsource (lib "Connectors") (part "1731721"))
    )
    (comp (ref "X21")
      (value "X")
      (footprint "691352710002")
      (description "TERM BLOCK PLUG 2POS STR 5MM")
      (fields
        (field (name "02. DISTRIBUTOR PART NUMBER") "732-2775-ND")
        (field (name "07. MANUFACTURER  PART NUMBER") "691352710002")
        (field (name "13. CREATED DATE/NAME") "??? / Hören")
      )
      (libsource (lib "PCB-Tester-Board-V1") (part "691352710002"))
    )
    (comp (ref "X22")
      (value "X")
      (footprint "691312710002")
      (description "TERM BLOCK HDR 2POS 90DEG 5MM")
      (fields
        (field (name "02. DISTRIBUTOR PART NUMBER") "732-2805-ND")
        (field (name "07. MANUFACTURER  PART NUMBER") "691312710002")
        (field (name "13. CREATED DATE/NAME") "??? / Hören")
      )
      (libsource (lib "Connectors") (part "691312710002"))
    )
    (comp (ref "X23")
      (value "X")
      (footprint "1731721")
      (description "TERM BLK 2P SIDE ENT 7.62MM PCB")
      (fields
        (field (name "02. DISTRIBUTOR PART NUMBER") "277-5849-ND")
        (field (name "07. MANUFACTURER  PART NUMBER") "1731721")
        (field (name "13. CREATED DATE/NAME") "JAN 2019 / Hören")
      )
      (libsource (lib "Connectors") (part "1731721"))
    )
    (comp (ref "X24")
      (value "X")
      (footprint "691312710002")
      (description "TERM BLOCK HDR 2POS 90DEG 5MM")
      (fields
        (field (name "02. DISTRIBUTOR PART NUMBER") "732-2805-ND")
        (field (name "07. MANUFACTURER  PART NUMBER") "691312710002")
        (field (name "13. CREATED DATE/NAME") "??? / Hören")
      )
      (libsource (lib "Connectors") (part "691312710002"))
    )
    (comp (ref "X25")
      (value "X")
      (footprint "691352710002")
      (description "TERM BLOCK PLUG 2POS STR 5MM")
      (fields
        (field (name "02. DISTRIBUTOR PART NUMBER") "732-2775-ND")
        (field (name "07. MANUFACTURER  PART NUMBER") "691352710002")
        (field (name "13. CREATED DATE/NAME") "??? / Hören")
      )
      (libsource (lib "PCB-Tester-Board-V1") (part "691352710002"))
    )
    (comp (ref "X26")
      (value "X")
      (footprint "1731721")
      (description "TERM BLK 2P SIDE ENT 7.62MM PCB")
      (fields
        (field (name "02. DISTRIBUTOR PART NUMBER") "277-5849-ND")
        (field (name "07. MANUFACTURER  PART NUMBER") "1731721")
        (field (name "13. CREATED DATE/NAME") "JAN 2019 / Hören")
      )
      (libsource (lib "Connectors") (part "1731721"))
    )
    (comp (ref "X27")
      (value "X")
      (footprint "691352710002")
      (description "TERM BLOCK PLUG 2POS STR 5MM")
      (fields
        (field (name "02. DISTRIBUTOR PART NUMBER") "732-2775-ND")
        (field (name "07. MANUFACTURER  PART NUMBER") "691352710002")
        (field (name "13. CREATED DATE/NAME") "??? / Hören")
      )
      (libsource (lib "PCB-Tester-Board-V1") (part "691352710002"))
    )
  )
  (nets
    (net (code "88") (name "/DRV24") (class "Default")
      (node (ref "Q12") (pin "1") (pinfunction "G_1") (pintype "passive"))
      (node (ref "R17") (pin "2") (pinfunction "2_2") (pintype "passive"))
    )
    (net (code "89") (name "/DRV25") (class "Default")
      (node (ref "Q13") (pin "1") (pinfunction "G_1") (pintype "passive"))
      (node (ref "R18") (pin "2") (pinfunction "2_2") (pintype "passive"))
    )
    (net (code "90") (name "/DRV26") (class "Default")
      (node (ref "Q14") (pin "1") (pinfunction "G_1") (pintype "passive"))
      (node (ref "R19") (pin "2") (pinfunction "2_2") (pintype "passive"))
    )
    (net (code "91") (name "/DRV27") (class "Default")
      (node (ref "Q15") (pin "1") (pinfunction "G_1") (pintype "passive"))
      (node (ref "R20") (pin "2") (pinfunction "2_2") (pintype "passive"))
    )
    (net (code "92") (name "/DRV28") (class "Default")
      (node (ref "Q16") (pin "1") (pinfunction "G_1") (pintype "passive"))
      (node (ref "R21") (pin "2") (pinfunction "2_2") (pintype "passive"))
    )
    (net (code "93") (name "/DRV29") (class "Default")
      (node (ref "Q17") (pin "1") (pinfunction "G_1") (pintype "passive"))
      (node (ref "R22") (pin "2") (pinfunction "2_2") (pintype "passive"))
    )
    (net (code "94") (name "/DRV30") (class "Default")
      (node (ref "Q18") (pin "1") (pinfunction "G_1") (pintype "passive"))
      (node (ref "R23") (pin "2") (pinfunction "2_2") (pintype "passive"))
    )
    (net (code "95") (name "/DRV31") (class "Default")
      (node (ref "Q19") (pin "1") (pinfunction "G_1") (pintype "passive"))
      (node (ref "R24") (pin "2") (pinfunction "2_2") (pintype "passive"))
    )
    (net (code "96") (name "/DRV32") (class "Default")
      (node (ref "Q20") (pin "1") (pinfunction "G_1") (pintype "passive"))
      (node (ref "R25") (pin "2") (pinfunction "2_2") (pintype "passive"))
    )
    (net (code "97") (name "/DRV33") (class "Default")
      (node (ref "Q21") (pin "1") (pinfunction "G_1") (pintype "passive"))
      (node (ref "R26") (pin "2") (pinfunction "2_2") (pintype "passive"))
    )
    (net (code "98") (name "/DRV34") (class "Default")
      (node (ref "Q22") (pin "1") (pinfunction "G_1") (pintype "passive"))
      (node (ref "R27") (pin "2") (pinfunction "2_2") (pintype "passive"))
    )
    (net (code "99") (name "/DRV35") (class "Default")
      (node (ref "Q23") (pin "1") (pinfunction "G_1") (pintype "passive"))
      (node (ref "R28") (pin "2") (pinfunction "2_2") (pintype "passive"))
    )
    (net (code "100") (name "/DRV36") (class "Default")
      (node (ref "Q24") (pin "1") (pinfunction "G_1") (pintype "passive"))
      (node (ref "R29") (pin "2") (pinfunction "2_2") (pintype "passive"))
    )
    (net (code "101") (name "/DRV37") (class "Default")
      (node (ref "Q25") (pin "1") (pinfunction "G_1") (pintype "passive"))
      (node (ref "R30") (pin "2") (pinfunction "2_2") (pintype "passive"))
    )
    (net (code "102") (name "/DRV38") (class "Default")
      (node (ref "Q26") (pin "1") (pinfunction "G_1") (pintype "passive"))
      (node (ref "R31") (pin "2") (pinfunction "2_2") (pintype "passive"))
    )
    (net (code "103") (name "/DRV39") (class "Default")
      (node (ref "Q11") (pin "1") (pinfunction "G_1") (pintype "passive"))
      (node (ref "R16") (pin "2") (pinfunction "2_2") (pintype "passive"))
    )
    (net (code "105") (name "5V0R") (class "Default")
      (node (ref "D14") (pin "2") (pinfunction "C_2") (pintype "passive"))
      (node (ref "D15") (pin "2") (pinfunction "C_2") (pintype "passive"))
      (node (ref "D16") (pin "2") (pinfunction "C_2") (pintype "passive"))
      (node (ref "D17") (pin "2") (pinfunction "C_2") (pintype "passive"))
      (node (ref "D18") (pin "2") (pinfunction "C_2") (pintype "passive"))
      (node (ref "D19") (pin "2") (pinfunction "C_2") (pintype "passive"))
      (node (ref "D20") (pin "2") (pinfunction "C_2") (pintype "passive"))
      (node (ref "D21") (pin "2") (pinfunction "C_2") (pintype "passive"))
      (node (ref "D22") (pin "2") (pinfunction "C_2") (pintype "passive"))
      (node (ref "D23") (pin "2") (pinfunction "C_2") (pintype "passive"))
      (node (ref "D24") (pin "2") (pinfunction "C_2") (pintype "passive"))
      (node (ref "D25") (pin "2") (pinfunction "C_2") (pintype "passive"))
      (node (ref "D26") (pin "2") (pinfunction "C_2") (pintype "passive"))
      (node (ref "D27") (pin "2") (pinfunction "C_2") (pintype "passive"))
      (node (ref "D28") (pin "2") (pinfunction "C_2") (pintype "passive"))
      (node (ref "D29") (pin "2") (pinfunction "C_2") (pintype "passive"))
      (node (ref "K12") (pin "1") (pinfunction "+_1") (pintype "passive"))
      (node (ref "K13") (pin "1") (pinfunction "+_1") (pintype "passive"))
      (node (ref "K14") (pin "1") (pinfunction "+_1") (pintype "passive"))
      (node (ref "K15") (pin "1") (pinfunction "+_1") (pintype "passive"))
      (node (ref "K16") (pin "1") (pinfunction "+_1") (pintype "passive"))
      (node (ref "K17") (pin "1") (pinfunction "+_1") (pintype "passive"))
      (node (ref "K18") (pin "1") (pinfunction "+_1") (pintype "passive"))
      (node (ref "K19") (pin "1") (pinfunction "+_1") (pintype "passive"))
      (node (ref "K20") (pin "1") (pinfunction "+_1") (pintype "passive"))
      (node (ref "K21") (pin "1") (pinfunction "+_1") (pintype "passive"))
      (node (ref "K22") (pin "1") (pinfunction "+_1") (pintype "passive"))
      (node (ref "K23") (pin "1") (pinfunction "+_1") (pintype "passive"))
      (node (ref "K24") (pin "1") (pinfunction "+_1") (pintype "passive"))
      (node (ref "K25") (pin "1") (pinfunction "+_1") (pintype "passive"))
      (node (ref "K26") (pin "1") (pinfunction "+_1") (pintype "passive"))
      (node (ref "K27") (pin "1") (pinfunction "+_1") (pintype "passive"))
    )
    (net (code "106") (name "GND") (class "Default")
      (node (ref "Q11") (pin "2") (pinfunction "S_2") (pintype "passive"))
      (node (ref "Q12") (pin "2") (pinfunction "S_2") (pintype "passive"))
      (node (ref "Q13") (pin "2") (pinfunction "S_2") (pintype "passive"))
      (node (ref "Q14") (pin "2") (pinfunction "S_2") (pintype "passive"))
      (node (ref "Q15") (pin "2") (pinfunction "S_2") (pintype "passive"))
      (node (ref "Q16") (pin "2") (pinfunction "S_2") (pintype "passive"))
      (node (ref "Q17") (pin "2") (pinfunction "S_2") (pintype "passive"))
      (node (ref "Q18") (pin "2") (pinfunction "S_2") (pintype "passive"))
      (node (ref "Q19") (pin "2") (pinfunction "S_2") (pintype "passive"))
      (node (ref "Q20") (pin "2") (pinfunction "S_2") (pintype "passive"))
      (node (ref "Q21") (pin "2") (pinfunction "S_2") (pintype "passive"))
      (node (ref "Q22") (pin "2") (pinfunction "S_2") (pintype "passive"))
      (node (ref "Q23") (pin "2") (pinfunction "S_2") (pintype "passive"))
      (node (ref "Q24") (pin "2") (pinfunction "S_2") (pintype "passive"))
      (node (ref "Q25") (pin "2") (pinfunction "S_2") (pintype "passive"))
      (node (ref "Q26") (pin "2") (pinfunction "S_2") (pintype "passive"))
      (node (ref "R16") (pin "1") (pinfunction "1_1") (pintype "passive"))
      (node (ref "R17") (pin "1") (pinfunction "1_1") (pintype "passive"))
      (node (ref "R18") (pin "1") (pinfunction "1_1") (pintype "passive"))
      (node (ref "R19") (pin "1") (pinfunction "1_1") (pintype "passive"))
      (node (ref "R20") (pin "1") (pinfunction "1_1") (pintype "passive"))
      (node (ref "R21") (pin "1") (pinfunction "1_1") (pintype "passive"))
      (node (ref "R22") (pin "1") (pinfunction "1_1") (pintype "passive"))
      (node (ref "R23") (pin "1") (pinfunction "1_1") (pintype "passive"))
      (node (ref "R24") (pin "1") (pinfunction "1_1") (pintype "passive"))
      (node (ref "R25") (pin "1") (pinfunction "1_1") (pintype "passive"))
      (node (ref "R26") (pin "1") (pinfunction "1_1") (pintype "passive"))
      (node (ref "R27") (pin "1") (pinfunction "1_1") (pintype "passive"))
      (node (ref "R28") (pin "1") (pinfunction "1_1") (pintype "passive"))
      (node (ref "R29") (pin "1") (pinfunction "1_1") (pintype "passive"))
      (node (ref "R30") (pin "1") (pinfunction "1_1") (pintype "passive"))
      (node (ref "R31") (pin "1") (pinfunction "1_1") (pintype "passive"))
    )
    (net (code "107") (name "Net-(D14-A)") (class "Default")
      (node (ref "D14") (pin "1") (pinfunction "A_1") (pintype "passive"))
      (node (ref "K12") (pin "5") (pinfunction "-_5") (pintype "passive"))
      (node (ref "Q12") (pin "3") (pinfunction "D_3") (pintype "passive"))
    )
    (net (code "108") (name "Net-(D15-A)") (class "Default")
      (node (ref "D15") (pin "1") (pinfunction "A_1") (pintype "passive"))
      (node (ref "K13") (pin "5") (pinfunction "-_5") (pintype "passive"))
      (node (ref "Q13") (pin "3") (pinfunction "D_3") (pintype "passive"))
    )
    (net (code "109") (name "Net-(D16-A)") (class "Default")
      (node (ref "D16") (pin "1") (pinfunction "A_1") (pintype "passive"))
      (node (ref "K14") (pin "5") (pinfunction "-_5") (pintype "passive"))
      (node (ref "Q14") (pin "3") (pinfunction "D_3") (pintype "passive"))
    )
    (net (code "110") (name "Net-(D17-A)") (class "Default")
      (node (ref "D17") (pin "1") (pinfunction "A_1") (pintype "passive"))
      (node (ref "K15") (pin "5") (pinfunction "-_5") (pintype "passive"))
      (node (ref "Q15") (pin "3") (pinfunction "D_3") (pintype "passive"))
    )
    (net (code "111") (name "Net-(D18-A)") (class "Default")
      (node (ref "D18") (pin "1") (pinfunction "A_1") (pintype "passive"))
      (node (ref "K16") (pin "5") (pinfunction "-_5") (pintype "passive"))
      (node (ref "Q16") (pin "3") (pinfunction "D_3") (pintype "passive"))
    )
    (net (code "112") (name "Net-(D19-A)") (class "Default")
      (node (ref "D19") (pin "1") (pinfunction "A_1") (pintype "passive"))
      (node (ref "K17") (pin "5") (pinfunction "-_5") (pintype "passive"))
      (node (ref "Q17") (pin "3") (pinfunction "D_3") (pintype "passive"))
    )
    (net (code "113") (name "Net-(D20-A)") (class "Default")
      (node (ref "D20") (pin "1") (pinfunction "A_1") (pintype "passive"))
      (node (ref "K18") (pin "5") (pinfunction "-_5") (pintype "passive"))
      (node (ref "Q18") (pin "3") (pinfunction "D_3") (pintype "passive"))
    )
    (net (code "114") (name "Net-(D21-A)") (class "Default")
      (node (ref "D21") (pin "1") (pinfunction "A_1") (pintype "passive"))
      (node (ref "K19") (pin "5") (pinfunction "-_5") (pintype "passive"))
      (node (ref "Q19") (pin "3") (pinfunction "D_3") (pintype "passive"))
    )
    (net (code "115") (name "Net-(D22-A)") (class "Default")
      (node (ref "D22") (pin "1") (pinfunction "A_1") (pintype "passive"))
      (node (ref "K20") (pin "5") (pinfunction "-_5") (pintype "passive"))
      (node (ref "Q20") (pin "3") (pinfunction "D_3") (pintype "passive"))
    )
    (net (code "116") (name "Net-(D23-A)") (class "Default")
      (node (ref "D23") (pin "1") (pinfunction "A_1") (pintype "passive"))
      (node (ref "K21") (pin "5") (pinfunction "-_5") (pintype "passive"))
      (node (ref "Q21") (pin "3") (pinfunction "D_3") (pintype "passive"))
    )
    (net (code "117") (name "Net-(D24-A)") (class "Default")
      (node (ref "D24") (pin "1") (pinfunction "A_1") (pintype "passive"))
      (node (ref "K22") (pin "5") (pinfunction "-_5") (pintype "passive"))
      (node (ref "Q22") (pin "3") (pinfunction "D_3") (pintype "passive"))
    )
    (net (code "118") (name "Net-(D25-A)") (class "Default")
      (node (ref "D25") (pin "1") (pinfunction "A_1") (pintype "passive"))
      (node (ref "K23") (pin "5") (pinfunction "-_5") (pintype "passive"))
      (node (ref "Q23") (pin "3") (pinfunction "D_3") (pintype "passive"))
    )
    (net (code "119") (name "Net-(D26-A)") (class "Default")
      (node (ref "D26") (pin "1") (pinfunction "A_1") (pintype "passive"))
      (node (ref "K24") (pin "5") (pinfunction "-_5") (pintype "passive"))
      (node (ref "Q24") (pin "3") (pinfunction "D_3") (pintype "passive"))
    )
    (net (code "120") (name "Net-(D27-A)") (class "Default")
      (node (ref "D27") (pin "1") (pinfunction "A_1") (pintype "passive"))
      (node (ref "K25") (pin "5") (pinfunction "-_5") (pintype "passive"))
      (node (ref "Q25") (pin "3") (pinfunction "D_3") (pintype "passive"))
    )
    (net (code "121") (name "Net-(D28-A)") (class "Default")
      (node (ref "D28") (pin "1") (pinfunction "A_1") (pintype "passive"))
      (node (ref "K26") (pin "5") (pinfunction "-_5") (pintype "passive"))
      (node (ref "Q26") (pin "3") (pinfunction "D_3") (pintype "passive"))
    )
    (net (code "122") (name "Net-(D29-A)") (class "Default")
      (node (ref "D29") (pin "1") (pinfunction "A_1") (pintype "passive"))
      (node (ref "K27") (pin "5") (pinfunction "-_5") (pintype "passive"))
      (node (ref "Q11") (pin "3") (pinfunction "D_3") (pintype "passive"))
    )
    (net (code "123") (name "Net-(K12A-Cin)") (class "Default")
      (node (ref "K12") (pin "2") (pinfunction "Cin_2") (pintype "passive"))
      (node (ref "X6") (pin "1") (pinfunction "+_1") (pintype "passive"))
    )
    (net (code "124") (name "Net-(K12A-Cno)") (class "Default")
      (node (ref "K12") (pin "3") (pinfunction "Cno_3") (pintype "passive"))
      (node (ref "X5") (pin "2") (pinfunction "2_2") (pintype "passive"))
    )
    (net (code "125") (name "Net-(K13A-Cin)") (class "Default")
      (node (ref "K13") (pin "2") (pinfunction "Cin_2") (pintype "passive"))
      (node (ref "X6") (pin "2") (pinfunction "-_2") (pintype "passive"))
    )
    (net (code "126") (name "Net-(K13A-Cno)") (class "Default")
      (node (ref "K13") (pin "3") (pinfunction "Cno_3") (pintype "passive"))
      (node (ref "X5") (pin "1") (pinfunction "1_1") (pintype "passive"))
    )
    (net (code "127") (name "Net-(K14A-Cin)") (class "Default")
      (node (ref "K14") (pin "2") (pinfunction "Cin_2") (pintype "passive"))
      (node (ref "X9") (pin "1") (pinfunction "+_1") (pintype "passive"))
    )
    (net (code "128") (name "Net-(K14A-Cno)") (class "Default")
      (node (ref "K14") (pin "3") (pinfunction "Cno_3") (pintype "passive"))
      (node (ref "X8") (pin "2") (pinfunction "2_2") (pintype "passive"))
    )
    (net (code "129") (name "Net-(K15A-Cin)") (class "Default")
      (node (ref "K15") (pin "2") (pinfunction "Cin_2") (pintype "passive"))
      (node (ref "X9") (pin "2") (pinfunction "-_2") (pintype "passive"))
    )
    (net (code "130") (name "Net-(K15A-Cno)") (class "Default")
      (node (ref "K15") (pin "3") (pinfunction "Cno_3") (pintype "passive"))
      (node (ref "X8") (pin "1") (pinfunction "1_1") (pintype "passive"))
    )
    (net (code "131") (name "Net-(K16A-Cin)") (class "Default")
      (node (ref "K16") (pin "2") (pinfunction "Cin_2") (pintype "passive"))
      (node (ref "X12") (pin "1") (pinfunction "+_1") (pintype "passive"))
    )
    (net (code "132") (name "Net-(K16A-Cno)") (class "Default")
      (node (ref "K16") (pin "3") (pinfunction "Cno_3") (pintype "passive"))
      (node (ref "X11") (pin "2") (pinfunction "2_2") (pintype "passive"))
    )
    (net (code "133") (name "Net-(K17A-Cin)") (class "Default")
      (node (ref "K17") (pin "2") (pinfunction "Cin_2") (pintype "passive"))
      (node (ref "X12") (pin "2") (pinfunction "-_2") (pintype "passive"))
    )
    (net (code "134") (name "Net-(K17A-Cno)") (class "Default")
      (node (ref "K17") (pin "3") (pinfunction "Cno_3") (pintype "passive"))
      (node (ref "X11") (pin "1") (pinfunction "1_1") (pintype "passive"))
    )
    (net (code "135") (name "Net-(K18A-Cin)") (class "Default")
      (node (ref "K18") (pin "2") (pinfunction "Cin_2") (pintype "passive"))
      (node (ref "X13") (pin "1") (pinfunction "+_1") (pintype "passive"))
    )
    (net (code "136") (name "Net-(K18A-Cno)") (class "Default")
      (node (ref "K18") (pin "3") (pinfunction "Cno_3") (pintype "passive"))
      (node (ref "X14") (pin "2") (pinfunction "2_2") (pintype "passive"))
    )
    (net (code "137") (name "Net-(K19A-Cin)") (class "Default")
      (node (ref "K19") (pin "2") (pinfunction "Cin_2") (pintype "passive"))
      (node (ref "X13") (pin "2") (pinfunction "-_2") (pintype "passive"))
    )
    (net (code "138") (name "Net-(K19A-Cno)") (class "Default")
      (node (ref "K19") (pin "3") (pinfunction "Cno_3") (pintype "passive"))
      (node (ref "X14") (pin "1") (pinfunction "1_1") (pintype "passive"))
    )
    (net (code "139") (name "Net-(K20A-Cin)") (class "Default")
      (node (ref "K20") (pin "2") (pinfunction "Cin_2") (pintype "passive"))
      (node (ref "X16") (pin "1") (pinfunction "+_1") (pintype "passive"))
    )
    (net (code "140") (name "Net-(K20A-Cno)") (class "Default")
      (node (ref "K20") (pin "3") (pinfunction "Cno_3") (pintype "passive"))
      (node (ref "X18") (pin "2") (pinfunction "2_2") (pintype "passive"))
    )
    (net (code "141") (name "Net-(K21A-Cin)") (class "Default")
      (node (ref "K21") (pin "2") (pinfunction "Cin_2") (pintype "passive"))
      (node (ref "X16") (pin "2") (pinfunction "-_2") (pintype "passive"))
    )
    (net (code "142") (name "Net-(K21A-Cno)") (class "Default")
      (node (ref "K21") (pin "3") (pinfunction "Cno_3") (pintype "passive"))
      (node (ref "X18") (pin "1") (pinfunction "1_1") (pintype "passive"))
    )
    (net (code "143") (name "Net-(K22A-Cin)") (class "Default")
      (node (ref "K22") (pin "2") (pinfunction "Cin_2") (pintype "passive"))
      (node (ref "X19") (pin "1") (pinfunction "+_1") (pintype "passive"))
    )
    (net (code "144") (name "Net-(K22A-Cno)") (class "Default")
      (node (ref "K22") (pin "3") (pinfunction "Cno_3") (pintype "passive"))
      (node (ref "X20") (pin "2") (pinfunction "2_2") (pintype "passive"))
    )
    (net (code "145") (name "Net-(K23A-Cin)") (class "Default")
      (node (ref "K23") (pin "2") (pinfunction "Cin_2") (pintype "passive"))
      (node (ref "X19") (pin "2") (pinfunction "-_2") (pintype "passive"))
    )
    (net (code "146") (name "Net-(K23A-Cno)") (class "Default")
      (node (ref "K23") (pin "3") (pinfunction "Cno_3") (pintype "passive"))
      (node (ref "X20") (pin "1") (pinfunction "1_1") (pintype "passive"))
    )
    (net (code "147") (name "Net-(K24A-Cin)") (class "Default")
      (node (ref "K24") (pin "2") (pinfunction "Cin_2") (pintype "passive"))
      (node (ref "X22") (pin "1") (pinfunction "+_1") (pintype "passive"))
    )
    (net (code "148") (name "Net-(K24A-Cno)") (class "Default")
      (node (ref "K24") (pin "3") (pinfunction "Cno_3") (pintype "passive"))
      (node (ref "X23") (pin "2") (pinfunction "2_2") (pintype "passive"))
    )
    (net (code "149") (name "Net-(K25A-Cin)") (class "Default")
      (node (ref "K25") (pin "2") (pinfunction "Cin_2") (pintype "passive"))
      (node (ref "X22") (pin "2") (pinfunction "-_2") (pintype "passive"))
    )
    (net (code "150") (name "Net-(K25A-Cno)") (class "Default")
      (node (ref "K25") (pin "3") (pinfunction "Cno_3") (pintype "passive"))
      (node (ref "X23") (pin "1") (pinfunction "1_1") (pintype "passive"))
    )
    (net (code "151") (name "Net-(K26A-Cin)") (class "Default")
      (node (ref "K26") (pin "2") (pinfunction "Cin_2") (pintype "passive"))
      (node (ref "X24") (pin "1") (pinfunction "+_1") (pintype "passive"))
    )
    (net (code "152") (name "Net-(K26A-Cno)") (class "Default")
      (node (ref "K26") (pin "3") (pinfunction "Cno_3") (pintype "passive"))
      (node (ref "X26") (pin "2") (pinfunction "2_2") (pintype "passive"))
    )
    (net (code "153") (name "Net-(K27A-Cin)") (class "Default")
      (node (ref "K27") (pin "2") (pinfunction "Cin_2") (pintype "passive"))
      (node (ref "X24") (pin "2") (pinfunction "-_2") (pintype "passive"))
    )
    (net (code "154") (name "Net-(K27A-Cno)") (class "Default")
      (node (ref "K27") (pin "3") (pinfunction "Cno_3") (pintype "passive"))
      (node (ref "X26") (pin "1") (pinfunction "1_1") (pintype "passive"))
    )
    (net (code "155") (name "unconnected-(K12A-Cnc-Pad4)") (class "Default")
      (node (ref "K12") (pin "4") (pinfunction "Cnc_4") (pintype "passive+no_connect"))
    )
    (net (code "156") (name "unconnected-(K13A-Cnc-Pad4)") (class "Default")
      (node (ref "K13") (pin "4") (pinfunction "Cnc_4") (pintype "passive+no_connect"))
    )
    (net (code "157") (name "unconnected-(K14A-Cnc-Pad4)") (class "Default")
      (node (ref "K14") (pin "4") (pinfunction "Cnc_4") (pintype "passive+no_connect"))
    )
    (net (code "158") (name "unconnected-(K15A-Cnc-Pad4)") (class "Default")
      (node (ref "K15") (pin "4") (pinfunction "Cnc_4") (pintype "passive+no_connect"))
    )
    (net (code "159") (name "unconnected-(K16A-Cnc-Pad4)") (class "Default")
      (node (ref "K16") (pin "4") (pinfunction "Cnc_4") (pintype "passive+no_connect"))
    )
    (net (code "160") (name "unconnected-(K17A-Cnc-Pad4)") (class "Default")
      (node (ref "K17") (pin "4") (pinfunction "Cnc_4") (pintype "passive+no_connect"))
    )
    (net (code "161") (name "unconnected-(K18A-Cnc-Pad4)") (class "Default")
      (node (ref "K18") (pin "4") (pinfunction "Cnc_4") (pintype "passive+no_connect"))
    )
    (net (code "162") (name "unconnected-(K19A-Cnc-Pad4)") (class "Default")
      (node (ref "K19") (pin "4") (pinfunction "Cnc_4") (pintype "passive+no_connect"))
    )
    (net (code "163") (name "unconnected-(K20A-Cnc-Pad4)") (class "Default")
      (node (ref "K20") (pin "4") (pinfunction "Cnc_4") (pintype "passive+no_connect"))
    )
    (net (code "164") (name "unconnected-(K21A-Cnc-Pad4)") (class "Default")
      (node (ref "K21") (pin "4") (pinfunction "Cnc_4") (pintype "passive+no_connect"))
    )
    (net (code "165") (name "unconnected-(K22A-Cnc-Pad4)") (class "Default")
      (node (ref "K22") (pin "4") (pinfunction "Cnc_4") (pintype "passive+no_connect"))
    )
    (net (code "166") (name "unconnected-(K23A-Cnc-Pad4)") (class "Default")
      (node (ref "K23") (pin "4") (pinfunction "Cnc_4") (pintype "passive+no_connect"))
    )
    (net (code "167") (name "unconnected-(K24A-Cnc-Pad4)") (class "Default")
      (node (ref "K24") (pin "4") (pinfunction "Cnc_4") (pintype "passive+no_connect"))
    )
    (net (code "168") (name "unconnected-(K25A-Cnc-Pad4)") (class "Default")
      (node (ref "K25") (pin "4") (pinfunction "Cnc_4") (pintype "passive+no_connect"))
    )
    (net (code "169") (name "unconnected-(K26A-Cnc-Pad4)") (class "Default")
      (node (ref "K26") (pin "4") (pinfunction "Cnc_4") (pintype "passive+no_connect"))
    )
    (net (code "170") (name "unconnected-(K27A-Cnc-Pad4)") (class "Default")
      (node (ref "K27") (pin "4") (pinfunction "Cnc_4") (pintype "passive+no_connect"))
    )
  )
)
